# Charger.net
KiCad netlist of a schematic drawn in Altium Designer
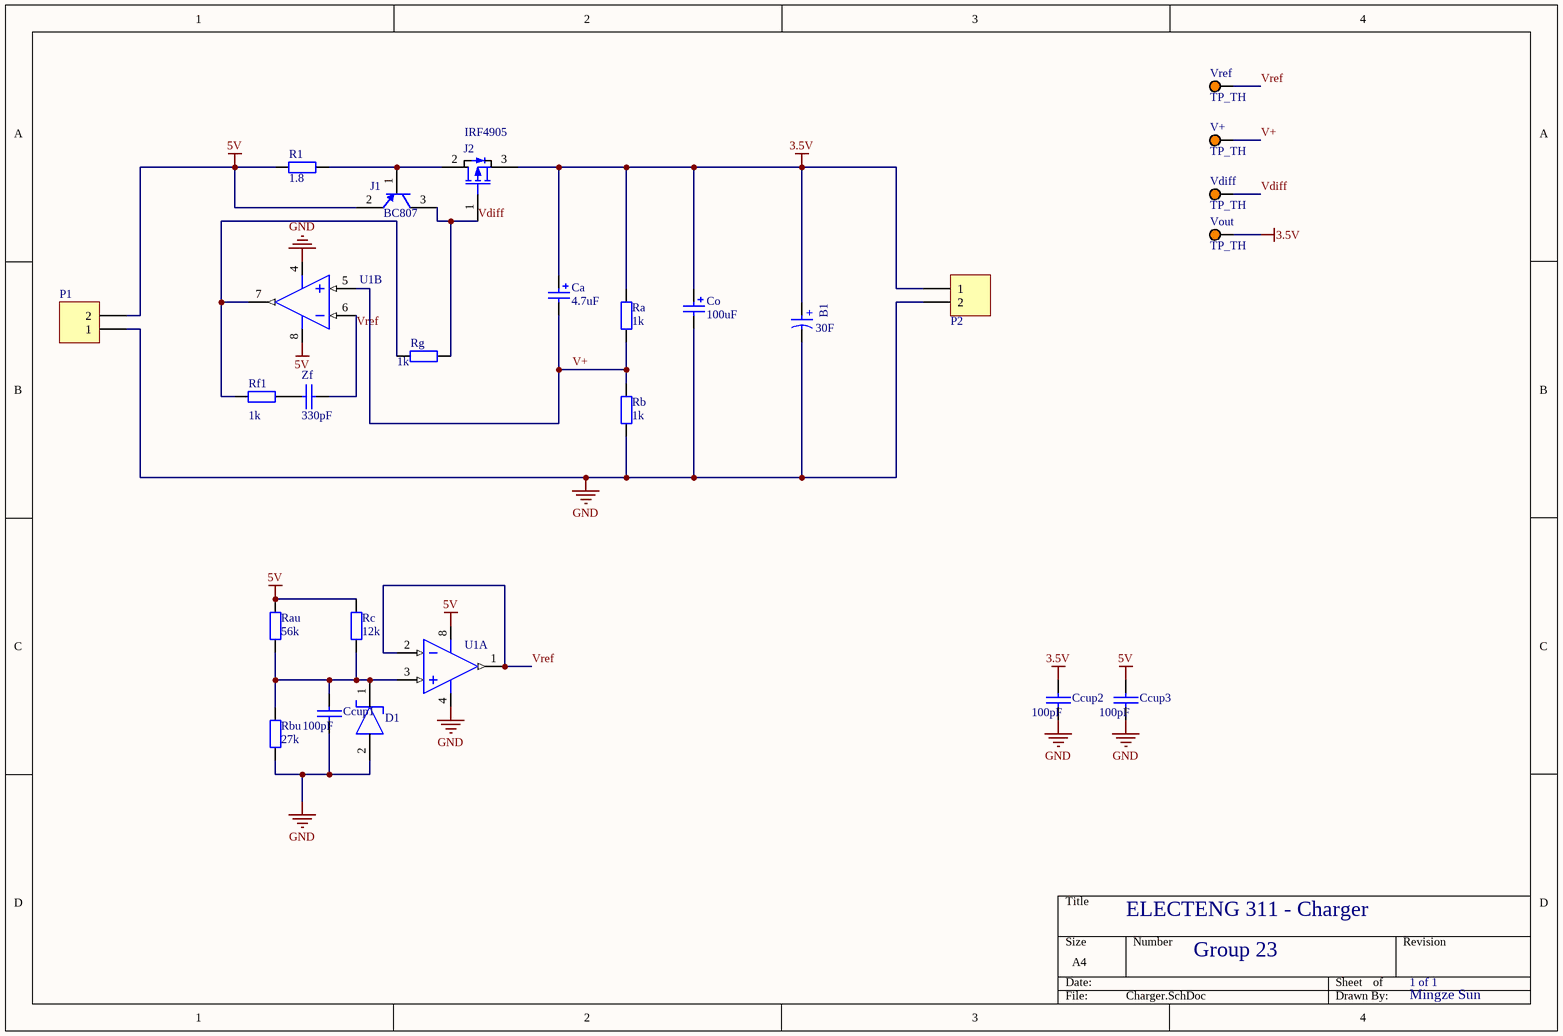
[diagram p0: Charger.SchDoc]

(export (version "E")
  (design (tool "Eeschema 10.0.6"))
  (components
    (comp (ref "B1")
      (value "860020474014")
      (footprint "WCAP-ATG5_D8H11.5")
      (description "Alum. Electrolytic Cap 470UF 25V 8MM Radial WCAP-ATG5, Lifetime 2000H +105OC")
      (fields (field (name "TOLERANCE") "20%") (field (name "CAPACITANCE") "30F"))
      (libsource (lib "Altium Content Vault") (part "Capacitor_Polarized"))
    )
    (comp (ref "Ca")
      (value "4.7uF")
      (footprint "ECE-CAPAE4X5.4SM")
      (description "CAP 4.7uF 35V ELE SM")
      (fields (field (name "Comment") "CAP000302"))
      (libsource (lib "UGs@UoA") (part "Cap Pol"))
    )
    (comp (ref "Ccup1")
      (value "100pF")
      (footprint "ECE-CAPC1608-0603SM")
      (description "CAP CER 100pF 50V NPO SM0603")
      (fields (field (name "Comment") "CAP000606"))
      (libsource (lib "UGs@UoA") (part "Cap"))
    )
    (comp (ref "Ccup2")
      (value "100pF")
      (footprint "ECE-CAPC1608-0603SM")
      (description "CAP CER 100pF 50V NPO SM0603")
      (fields (field (name "Comment") "CAP000606"))
      (libsource (lib "UGs@UoA") (part "Cap"))
    )
    (comp (ref "Ccup3")
      (value "100pF")
      (footprint "ECE-CAPC1608-0603SM")
      (description "CAP CER 100pF 50V NPO SM0603")
      (fields (field (name "Comment") "CAP000606"))
      (libsource (lib "UGs@UoA") (part "Cap"))
    )
    (comp (ref "Co")
      (value "100uF")
      (footprint "ECE-CAPAE6.3X5.4SM")
      (description "CAP 100uF 16V ELE SM")
      (fields (field (name "Comment") "CAP000306"))
      (libsource (lib "UGs@UoA") (part "Cap Pol"))
    )
    (comp (ref "D1")
      (value "SZESD8351XV2T1G")
      (footprint "FP-502-MFG")
      (description "SZESD8351XV2T1G SZESD8351 Series 11.2 V 5 A Surface Mount ESD Protection Diode - SOD-523")
      (libsource (lib "Altium Content Vault") (part "3fe65190a525cd526404b3758b91230"))
    )
    (comp (ref "J1")
      (value "BC807")
      (footprint "ECE-SOT23SM")
      (description "TRANS PNP GP 500MA 45V SOT23")
      (libsource (lib "UGs@UoA") (part "PNP Transistor 5"))
    )
    (comp (ref "J2")
      (value "IRF4905")
      (footprint "ECE-TO220ABTH")
      (description "P-Type MOSFET IRF4905 TH")
      (fields (field (name "Comment") "TRA000017"))
      (libsource (lib "UGs@UoA") (part "P-Type MOSFET"))
    )
    (comp (ref "P1")
      (value "CON000001")
      (footprint "ECE-600102STTH")
      (description "HEADER POLARISED 2WAY TH")
      (libsource (lib "") (part "Header 2_1"))
    )
    (comp (ref "P2")
      (value "CON000001")
      (footprint "ECE-600102STTH")
      (description "HEADER POLARISED 2WAY TH")
      (libsource (lib "UGs@UoA") (part "Header 2"))
    )
    (comp (ref "R1")
      (value "1.8")
      (footprint "ECE-RESA0.4TH")
      (description "RES MF 1R8 TH")
      (libsource (lib "") (part "Resistor_1"))
    )
    (comp (ref "Ra")
      (value "1k")
      (footprint "ECE-RESC1608-0603SM")
      (description "RES CER 1K 1608 SM")
      (fields (field (name "Comment") "RES000138"))
      (libsource (lib "UGs@UoA") (part "Resistor"))
    )
    (comp (ref "Rau")
      (value "56k")
      (footprint "ECE-RESC1608-0603SM")
      (description "RES CER 56K 1608 SM")
      (fields (field (name "Comment") "RES000159"))
      (libsource (lib "UGs@UoA") (part "Resistor"))
    )
    (comp (ref "Rb")
      (value "1k")
      (footprint "ECE-RESC1608-0603SM")
      (description "RES CER 1K 1608 SM")
      (fields (field (name "Comment") "RES000138"))
      (libsource (lib "UGs@UoA") (part "Resistor"))
    )
    (comp (ref "Rbu")
      (value "27k")
      (footprint "ECE-RESC1608-0603SM")
      (description "RES CER 27K 1608 SM")
      (fields (field (name "Comment") "RES000155"))
      (libsource (lib "UGs@UoA") (part "Resistor"))
    )
    (comp (ref "Rc")
      (value "12k")
      (footprint "ECE-RESC1608-0603SM")
      (description "RES CER 12K 1608 SM")
      (libsource (lib "") (part "Resistor_2"))
    )
    (comp (ref "Rf1")
      (value "1k")
      (footprint "ECE-RESC1608-0603SM")
      (description "RES CER 1K 1608 SM")
      (fields (field (name "Comment") "RES000138"))
      (libsource (lib "") (part "Resistor_1"))
    )
    (comp (ref "Rg")
      (value "1k")
      (footprint "ECE-RESC1608-0603SM")
      (description "RES CER 1K 1608 SM")
      (fields (field (name "Comment") "RES000138"))
      (libsource (lib "") (part "Resistor_1"))
    )
    (comp (ref "U1")
      (value "TLV9162IDR")
      (footprint "SOIC8-Ti-Footprint")
      (description "Dual 10pA 33V/us 11MHz SOIC-8 Operational Amplifier ROHS")
      (libsource (lib "UGs@UoA") (part "DualOpAmp"))
    )
    (comp (ref "V+")
      (value "TP_TH")
      (footprint "Test-Pin-TH")
      (description "Test pin TH generic")
      (libsource (lib "UGs@UoA") (part "Test Pin"))
    )
    (comp (ref "Vdiff")
      (value "TP_TH")
      (footprint "Test-Pin-TH")
      (description "Test pin TH generic")
      (libsource (lib "UGs@UoA") (part "Test Pin"))
    )
    (comp (ref "Vout")
      (value "TP_TH")
      (footprint "Test-Pin-TH")
      (description "Test pin TH generic")
      (libsource (lib "UGs@UoA") (part "Test Pin"))
    )
    (comp (ref "Vref")
      (value "TP_TH")
      (footprint "Test-Pin-TH")
      (description "Test pin TH generic")
      (libsource (lib "UGs@UoA") (part "Test Pin"))
    )
    (comp (ref "Zf")
      (value "330pF")
      (footprint "ECE-CAPC1608-0603SM")
      (description "CAP CER 330pF 50V X7R SM0603")
      (fields (field (name "Comment") "CAP000609"))
      (libsource (lib "UGs@UoA") (part "Cap"))
    )
  )
  (nets
    (net (code "1") (name "/V+") (class "Default")
      (node (ref "Ca") (pin "2") (pinfunction "2_2") (pintype "passive"))
      (node (ref "Ra") (pin "2") (pinfunction "2_2") (pintype "passive"))
      (node (ref "Rb") (pin "1") (pinfunction "1_1") (pintype "passive"))
      (node (ref "U1") (pin "5") (pinfunction "2IN+_5") (pintype "input"))
      (node (ref "V+") (pin "1") (pinfunction "1_1") (pintype "passive"))
    )
    (net (code "2") (name "/Vdiff") (class "Default")
      (node (ref "J1") (pin "3") (pinfunction "C_3") (pintype "passive"))
      (node (ref "J2") (pin "1") (pinfunction "G_1") (pintype "passive"))
      (node (ref "Rg") (pin "2") (pinfunction "2_2") (pintype "passive"))
      (node (ref "Vdiff") (pin "1") (pinfunction "1_1") (pintype "passive"))
    )
    (net (code "3") (name "/Vref") (class "Default")
      (node (ref "U1") (pin "1") (pinfunction "1OUT_1") (pintype "output"))
      (node (ref "U1") (pin "2") (pinfunction "1IN-_2") (pintype "input"))
      (node (ref "U1") (pin "6") (pinfunction "2IN-_6") (pintype "input"))
      (node (ref "Vref") (pin "1") (pinfunction "1_1") (pintype "passive"))
      (node (ref "Zf") (pin "1") (pinfunction "1_1") (pintype "passive"))
    )
    (net (code "4") (name "3.5V") (class "Default")
      (node (ref "B1") (pin "1") (pinfunction "P_1") (pintype "passive"))
      (node (ref "Ca") (pin "1") (pinfunction "1_1") (pintype "passive"))
      (node (ref "Ccup2") (pin "1") (pinfunction "1_1") (pintype "passive"))
      (node (ref "Co") (pin "1") (pinfunction "1_1") (pintype "passive"))
      (node (ref "J2") (pin "3") (pinfunction "S_3") (pintype "passive"))
      (node (ref "P2") (pin "1") (pinfunction "1_1") (pintype "passive"))
      (node (ref "Ra") (pin "1") (pinfunction "1_1") (pintype "passive"))
      (node (ref "Vout") (pin "1") (pinfunction "1_1") (pintype "passive"))
    )
    (net (code "5") (name "5V") (class "Default")
      (node (ref "Ccup3") (pin "1") (pinfunction "1_1") (pintype "passive"))
      (node (ref "J1") (pin "2") (pinfunction "E_2") (pintype "passive"))
      (node (ref "P1") (pin "2") (pinfunction "2_2") (pintype "passive"))
      (node (ref "R1") (pin "1") (pinfunction "1_1") (pintype "passive"))
      (node (ref "Rau") (pin "1") (pinfunction "1_1") (pintype "passive"))
      (node (ref "Rc") (pin "2") (pinfunction "2_2") (pintype "passive"))
      (node (ref "U1") (pin "8") (pinfunction "VCC_8") (pintype "power_in"))
    )
    (net (code "6") (name "GND") (class "Default")
      (node (ref "B1") (pin "2") (pinfunction "N_2") (pintype "passive"))
      (node (ref "Ccup1") (pin "2") (pinfunction "2_2") (pintype "passive"))
      (node (ref "Ccup2") (pin "2") (pinfunction "2_2") (pintype "passive"))
      (node (ref "Ccup3") (pin "2") (pinfunction "2_2") (pintype "passive"))
      (node (ref "Co") (pin "2") (pinfunction "2_2") (pintype "passive"))
      (node (ref "D1") (pin "2") (pinfunction "A_2") (pintype "passive"))
      (node (ref "P1") (pin "1") (pinfunction "1_1") (pintype "passive"))
      (node (ref "P2") (pin "2") (pinfunction "2_2") (pintype "passive"))
      (node (ref "Rb") (pin "2") (pinfunction "2_2") (pintype "passive"))
      (node (ref "Rbu") (pin "2") (pinfunction "2_2") (pintype "passive"))
      (node (ref "U1") (pin "4") (pinfunction "GND_4") (pintype "power_in"))
    )
    (net (code "7") (name "Net-(D1-C)") (class "Default")
      (node (ref "Ccup1") (pin "1") (pinfunction "1_1") (pintype "passive"))
      (node (ref "D1") (pin "1") (pinfunction "C_1") (pintype "passive"))
      (node (ref "Rau") (pin "2") (pinfunction "2_2") (pintype "passive"))
      (node (ref "Rbu") (pin "1") (pinfunction "1_1") (pintype "passive"))
      (node (ref "Rc") (pin "1") (pinfunction "1_1") (pintype "passive"))
      (node (ref "U1") (pin "3") (pinfunction "1IN+_3") (pintype "input"))
    )
    (net (code "8") (name "Net-(J1-B)") (class "Default")
      (node (ref "J1") (pin "1") (pinfunction "B_1") (pintype "passive"))
      (node (ref "J2") (pin "2") (pinfunction "D_2") (pintype "passive"))
      (node (ref "R1") (pin "2") (pinfunction "2_2") (pintype "passive"))
    )
    (net (code "9") (name "Net-(Rf1-Pad2)") (class "Default")
      (node (ref "Rf1") (pin "2") (pinfunction "2_2") (pintype "passive"))
      (node (ref "Zf") (pin "2") (pinfunction "2_2") (pintype "passive"))
    )
    (net (code "10") (name "Net-(U1B-2OUT)") (class "Default")
      (node (ref "Rf1") (pin "1") (pinfunction "1_1") (pintype "passive"))
      (node (ref "Rg") (pin "1") (pinfunction "1_1") (pintype "passive"))
      (node (ref "U1") (pin "7") (pinfunction "2OUT_7") (pintype "output"))
    )
  )
)
